# Sheet1.net
KiCad netlist of a schematic drawn in Altium Designer
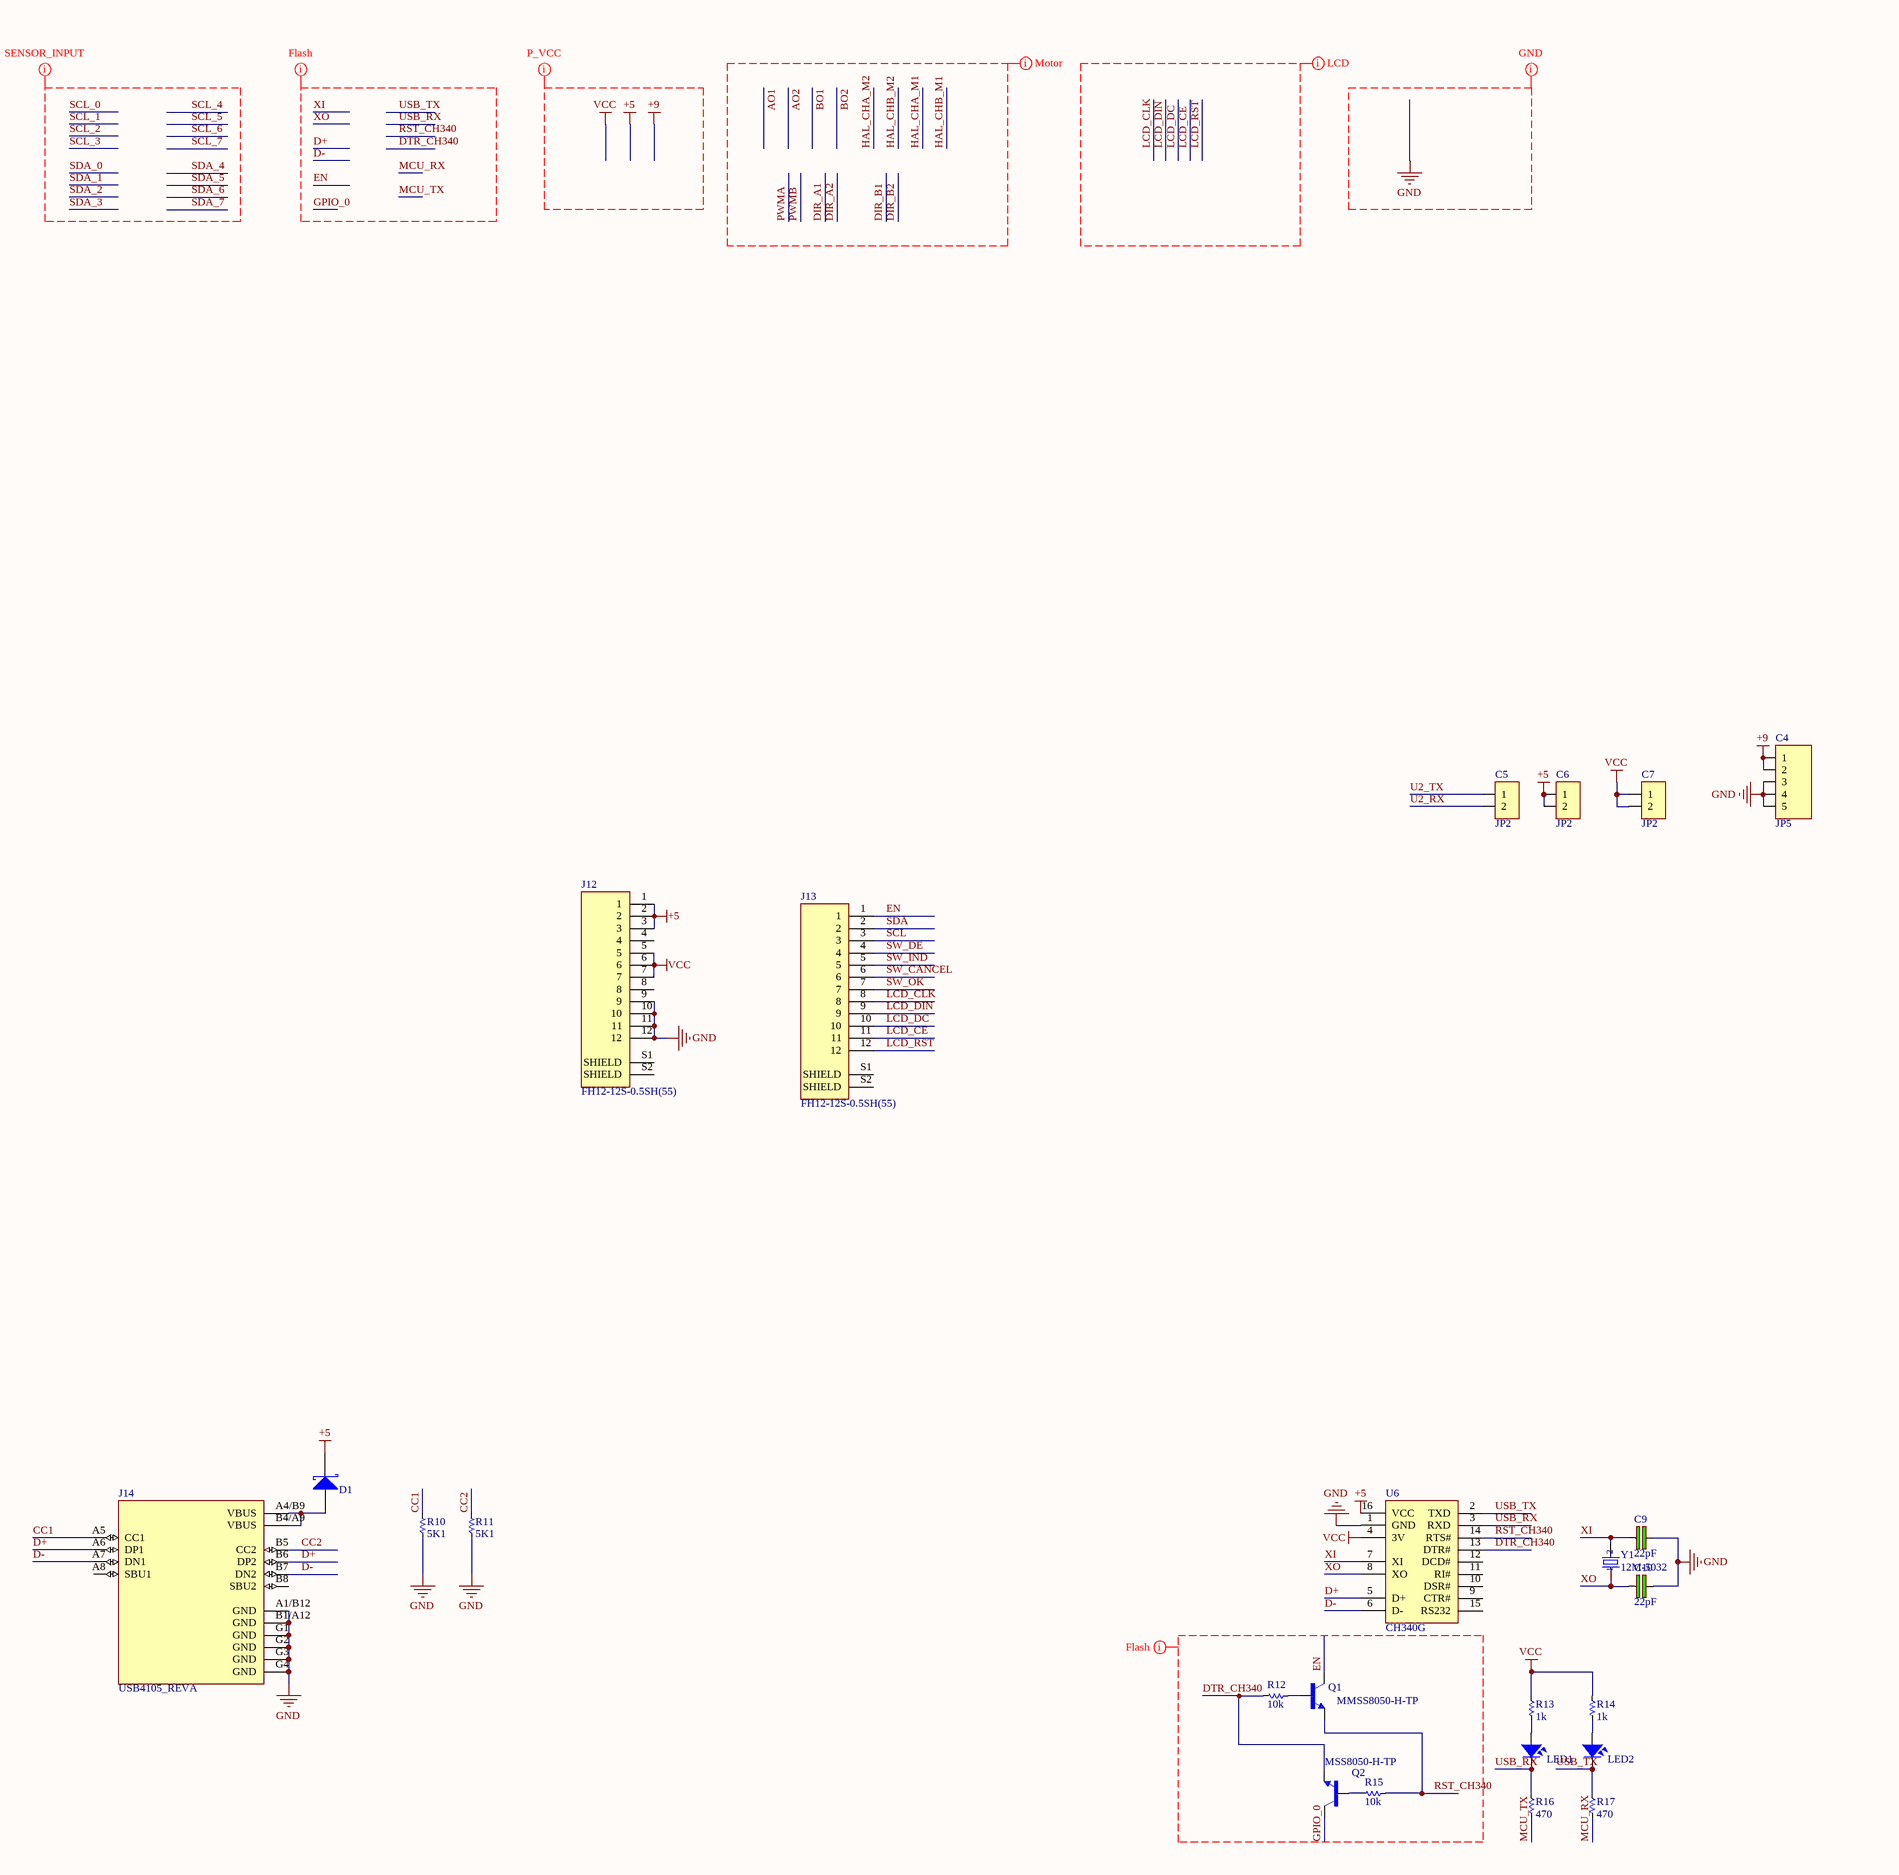
[diagram p0: Sheet1.SchDoc, left]
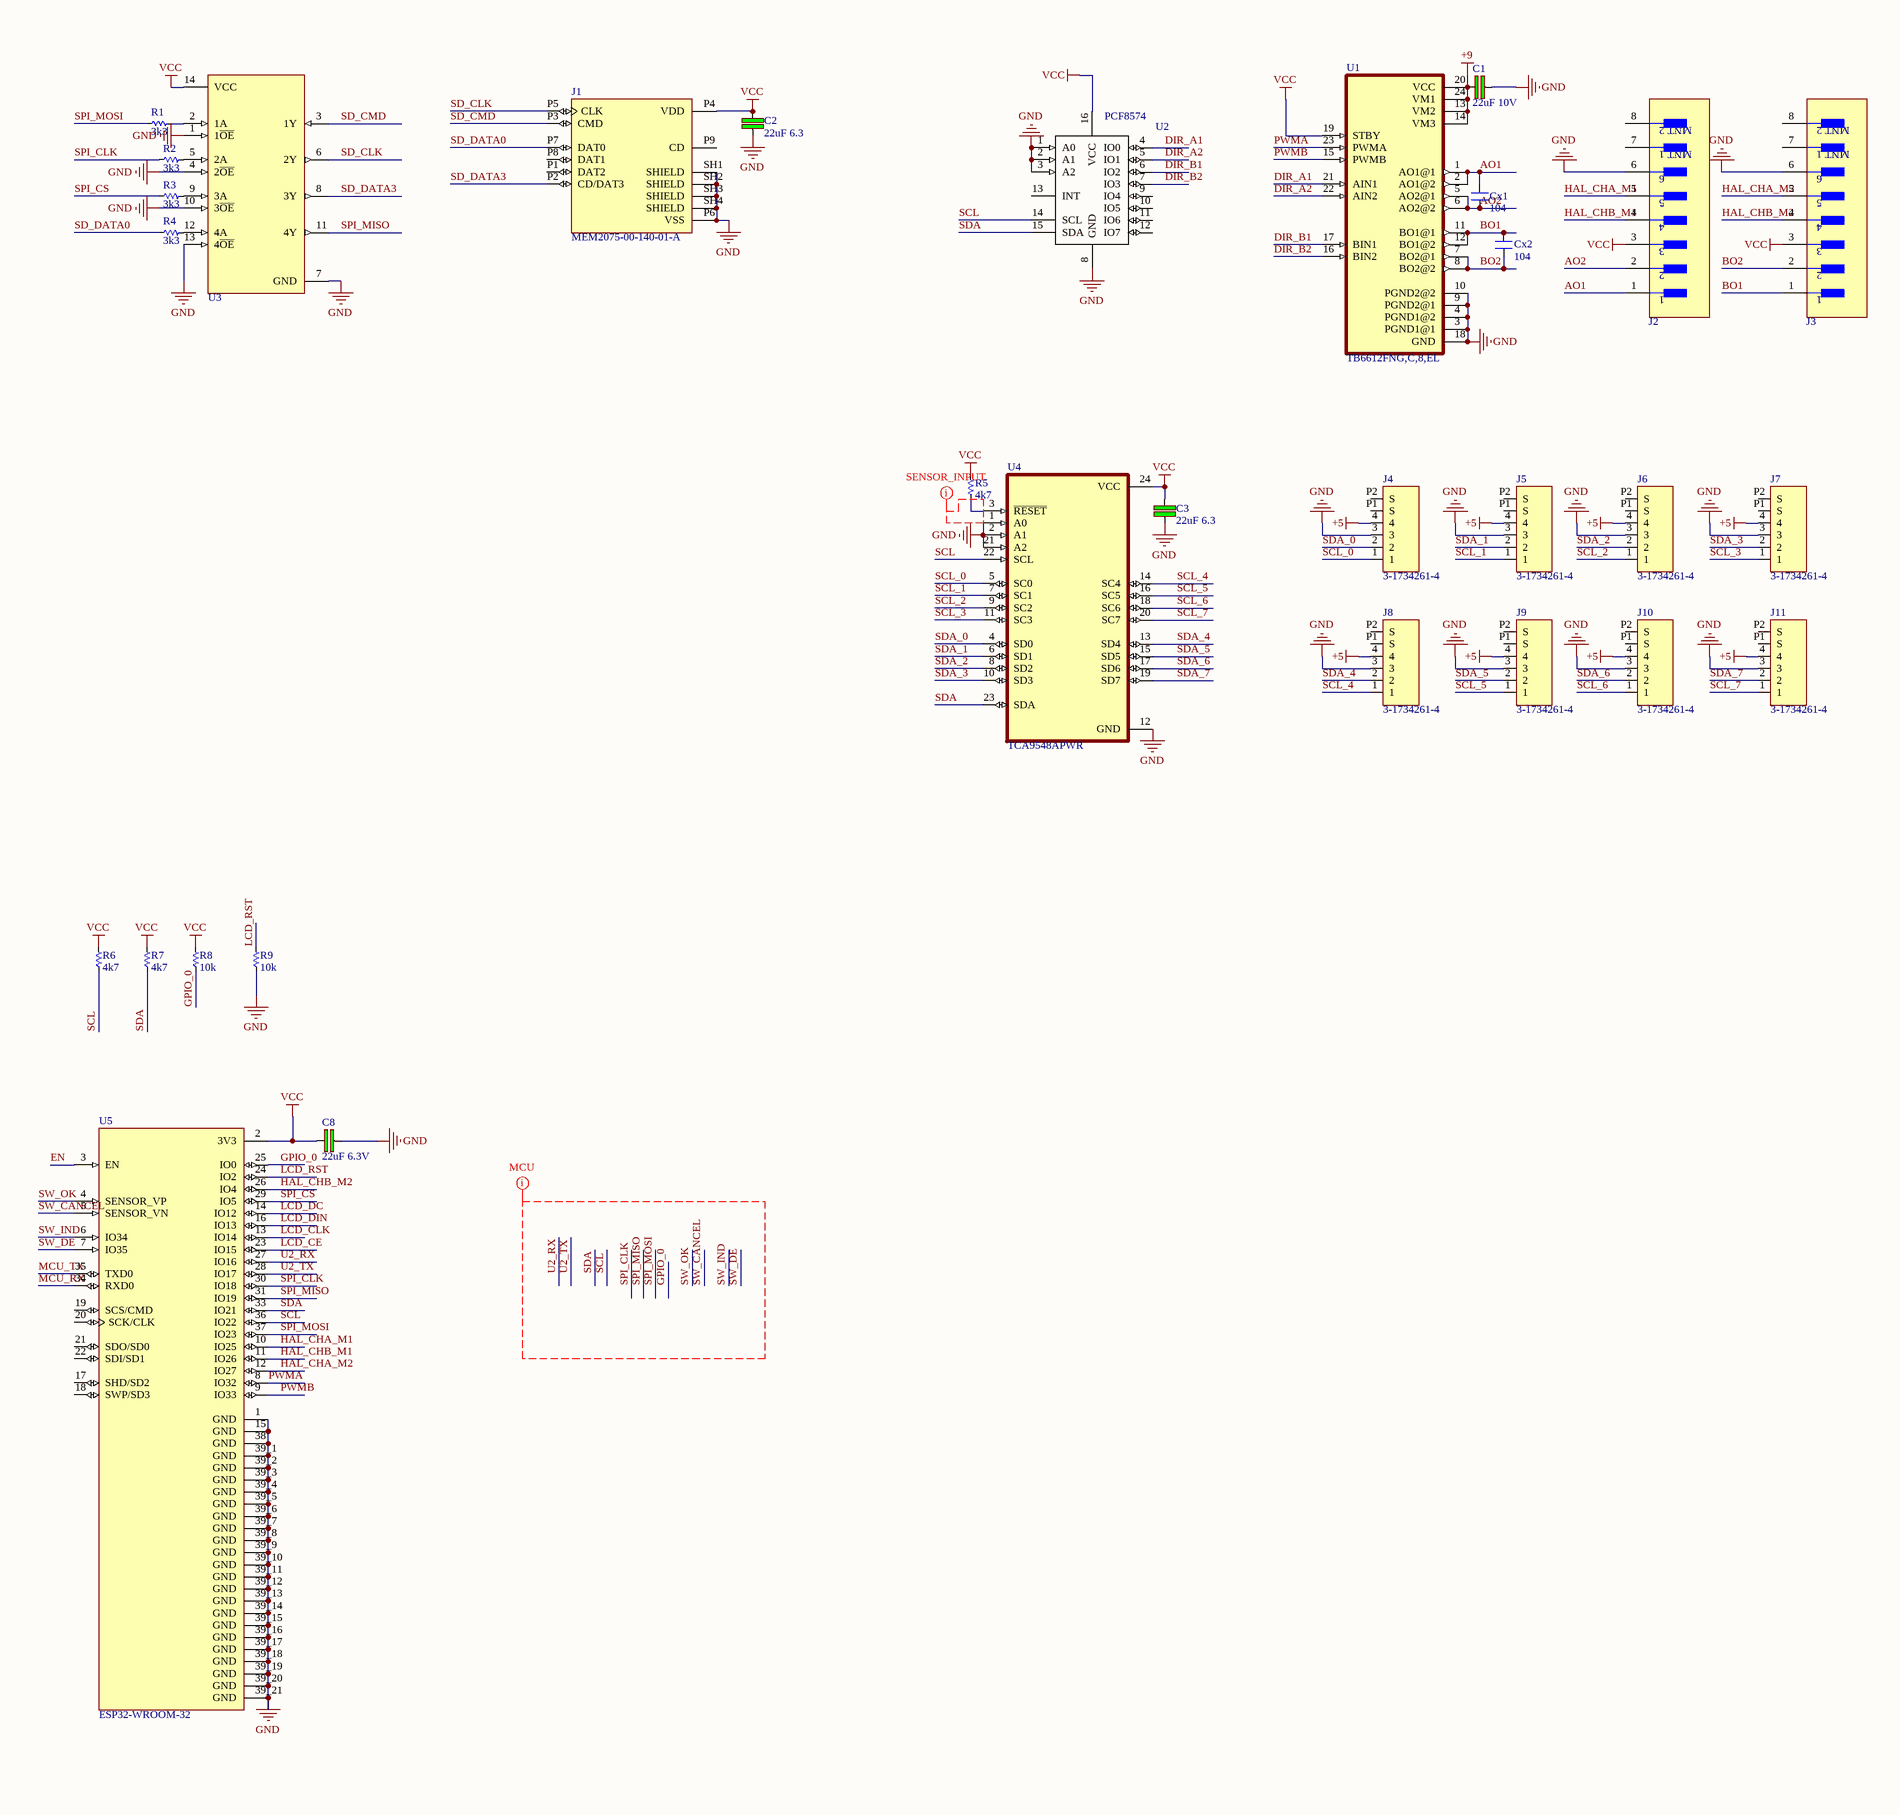
[diagram p1: Sheet1.SchDoc, right]

(export (version "E")
  (design (tool "Eeschema 10.0.6"))
  (components
    (comp (ref "C1")
      (value "22uF 10V")
      (footprint "CN-SMD-1206")
      (description "Cap SMD 1206 >5V")
      (libsource (lib "Library AL") (part "C"))
    )
    (comp (ref "C2")
      (value "22uF 6.3")
      (footprint "CN-SMD-1206")
      (description "Cap SMD 1206 >5V")
      (libsource (lib "") (part "C_2"))
    )
    (comp (ref "C3")
      (value "22uF 6.3")
      (footprint "CN-SMD-1206")
      (description "Cap SMD 1206 >5V")
      (libsource (lib "") (part "C_2"))
    )
    (comp (ref "C4")
      (value "JP5")
      (footprint "JP5-D1T")
      (description "WR-PHD 2.54 mm Angled Socket Header")
      (fields
        (field (name "MANUFACTURER") "Würth Elektronik eiSos GmbH")
        (field (name "PARTNO") "613005143121")
        (field (name "CREATED BY") "Karrer Zheng")
      )
      (libsource (lib "TechMT.VN_Lib_Project v2") (part "JP5"))
    )
    (comp (ref "C5")
      (value "JP2")
      (footprint "JP2-D1T")
      (description "WR-PHD 2.54 mm Angled Socket Header")
      (fields
        (field (name "MANUFACTURER") "Würth Elektronik eiSos GmbH")
        (field (name "PARTNO") "613002143121")
        (field (name "CREATED BY") "Karrer Zheng")
      )
      (libsource (lib "TechMT.VN_Lib_Project v2") (part "JP2"))
    )
    (comp (ref "C6")
      (value "JP2")
      (footprint "JP2-D1T")
      (description "WR-PHD 2.54 mm Angled Socket Header")
      (fields
        (field (name "MANUFACTURER") "Würth Elektronik eiSos GmbH")
        (field (name "PARTNO") "613002143121")
        (field (name "CREATED BY") "Karrer Zheng")
      )
      (libsource (lib "TechMT.VN_Lib_Project v2") (part "JP2"))
    )
    (comp (ref "C7")
      (value "JP2")
      (footprint "JP2-D1T")
      (description "WR-PHD 2.54 mm Angled Socket Header")
      (fields
        (field (name "MANUFACTURER") "Würth Elektronik eiSos GmbH")
        (field (name "PARTNO") "613002143121")
        (field (name "CREATED BY") "Karrer Zheng")
      )
      (libsource (lib "TechMT.VN_Lib_Project v2") (part "JP2"))
    )
    (comp (ref "C8")
      (value "22uF 6.3V")
      (footprint "CN-SMD-1206")
      (description "Cap SMD 1206 >5V")
      (libsource (lib "Library AL") (part "C"))
    )
    (comp (ref "C9")
      (value "22pF")
      (footprint "CN-SMD-0603")
      (description "Cap SMD")
      (libsource (lib "") (part "C_1"))
    )
    (comp (ref "C10")
      (value "22pF")
      (footprint "CN-SMD-0603")
      (description "Cap SMD")
      (libsource (lib "") (part "C_1"))
    )
    (comp (ref "Cx1") (value "104") (footprint "CN-SMD-0603") (libsource (lib "LIBRARY") (part "CN")))
    (comp (ref "Cx2") (value "104") (footprint "CN-SMD-0603") (libsource (lib "LIBRARY") (part "CN")))
    (comp (ref "D1")
      (value "D Schottky")
      (footprint "SS34")
      (description "Schottky Diode")
      (fields (field (name "PUBLISHER") "Altium Limited"))
      (libsource (lib "TechMT.VN_Lib_Project v1.0") (part "D Schottky"))
    )
    (comp (ref "J1")
      (value "MEM2075-00-140-01-A")
      (footprint "GCT_MEM2075-00-140-01-A")
      (description "9 _8 + 1_ Position Card Connector microSDâ„¢ Surface Mount, Right Angle Gold")
      (fields (field (name "MF") "Global Connector Technology"))
      (libsource (lib "micSDCARD01") (part "MEM2075-00-140-01-A"))
    )
    (comp (ref "J2")
      (value "532610671")
      (footprint "Molex_0_MFG")
      (libsource (lib "Conn_Molex_532610671_eec") (part "532610671"))
    )
    (comp (ref "J3")
      (value "532610671")
      (footprint "Molex_0_MFG")
      (libsource (lib "Conn_Molex_532610671_eec") (part "532610671"))
    )
    (comp (ref "J4")
      (value "3-1734261-4")
      (footprint "TE_3-1734261-4")
      (description "4ä½å•æŽ’1.25mmç›´è§’è¡¨é¢å®‰è£…æŽ¥å¤´è¿žæŽ¥å™¨")
      (fields (field (name "MF") "TE Connectivity"))
      (libsource (lib "hdr_4P_1.25m") (part "3-1734261-4"))
    )
    (comp (ref "J5")
      (value "3-1734261-4")
      (footprint "TE_3-1734261-4")
      (description "4ä½å•æŽ’1.25mmç›´è§’è¡¨é¢å®‰è£…æŽ¥å¤´è¿žæŽ¥å™¨")
      (fields (field (name "MF") "TE Connectivity"))
      (libsource (lib "hdr_4P_1.25m") (part "3-1734261-4"))
    )
    (comp (ref "J6")
      (value "3-1734261-4")
      (footprint "TE_3-1734261-4")
      (description "4ä½å•æŽ’1.25mmç›´è§’è¡¨é¢å®‰è£…æŽ¥å¤´è¿žæŽ¥å™¨")
      (fields (field (name "MF") "TE Connectivity"))
      (libsource (lib "hdr_4P_1.25m") (part "3-1734261-4"))
    )
    (comp (ref "J7")
      (value "3-1734261-4")
      (footprint "TE_3-1734261-4")
      (description "4ä½å•æŽ’1.25mmç›´è§’è¡¨é¢å®‰è£…æŽ¥å¤´è¿žæŽ¥å™¨")
      (fields (field (name "MF") "TE Connectivity"))
      (libsource (lib "hdr_4P_1.25m") (part "3-1734261-4"))
    )
    (comp (ref "J8")
      (value "3-1734261-4")
      (footprint "TE_3-1734261-4")
      (description "4ä½å•æŽ’1.25mmç›´è§’è¡¨é¢å®‰è£…æŽ¥å¤´è¿žæŽ¥å™¨")
      (fields (field (name "MF") "TE Connectivity"))
      (libsource (lib "hdr_4P_1.25m") (part "3-1734261-4"))
    )
    (comp (ref "J9")
      (value "3-1734261-4")
      (footprint "TE_3-1734261-4")
      (description "4ä½å•æŽ’1.25mmç›´è§’è¡¨é¢å®‰è£…æŽ¥å¤´è¿žæŽ¥å™¨")
      (fields (field (name "MF") "TE Connectivity"))
      (libsource (lib "hdr_4P_1.25m") (part "3-1734261-4"))
    )
    (comp (ref "J10")
      (value "3-1734261-4")
      (footprint "TE_3-1734261-4")
      (description "4ä½å•æŽ’1.25mmç›´è§’è¡¨é¢å®‰è£…æŽ¥å¤´è¿žæŽ¥å™¨")
      (fields (field (name "MF") "TE Connectivity"))
      (libsource (lib "hdr_4P_1.25m") (part "3-1734261-4"))
    )
    (comp (ref "J11")
      (value "3-1734261-4")
      (footprint "TE_3-1734261-4")
      (description "4ä½å•æŽ’1.25mmç›´è§’è¡¨é¢å®‰è£…æŽ¥å¤´è¿žæŽ¥å™¨")
      (fields (field (name "MF") "TE Connectivity"))
      (libsource (lib "hdr_4P_1.25m") (part "3-1734261-4"))
    )
    (comp (ref "J12")
      (value "FH12-12S-0.5SH(55)")
      (footprint "HIROSE_FH12-12S-0.5SH(55)")
      (description "12 Position FFC, FPC Connector Contacts, Bottom 0.020 _0.50mm_ Surface Mount, Right Angle")
      (fields (field (name "MF") "Hirose") (field (name "MP") "FH12-12S-0.5SH_55_"))
      (libsource (lib "FPC_SOC_12pos0.5") (part "FH12-12S-0.5SH(55)"))
    )
    (comp (ref "J13")
      (value "FH12-12S-0.5SH(55)")
      (footprint "HIROSE_FH12-12S-0.5SH(55)")
      (description "12 Position FFC, FPC Connector Contacts, Bottom 0.020 _0.50mm_ Surface Mount, Right Angle")
      (fields (field (name "MF") "Hirose") (field (name "MP") "FH12-12S-0.5SH_55_"))
      (libsource (lib "FPC_SOC_12pos0.5") (part "FH12-12S-0.5SH(55)"))
    )
    (comp (ref "J14")
      (value "USB4105_REVA")
      (footprint "GCT_USB4105_REVA")
      (fields (field (name "MF") "Global Connector Technology") (field (name "MP") "USB4105"))
      (libsource (lib "usb_typeC2.0B") (part "USB4105_REVA"))
    )
    (comp (ref "LED1")
      (value "LED")
      (footprint "LED-0805-Red")
      (libsource (lib "TechMT.VN_Lib_Project v2") (part "LED SMD"))
    )
    (comp (ref "LED2")
      (value "LED")
      (footprint "LED-0805-Red")
      (libsource (lib "TechMT.VN_Lib_Project v2") (part "LED SMD"))
    )
    (comp (ref "Q1")
      (value "MMSS8050-H-TP")
      (footprint "TRANS_MMSS8050-H-TP")
      (description "Bipolar _BJT_ Transistor NPN 25V 1.5A 100MHz 625mW Surface Mount SOT-23")
      (fields (field (name "MF") "Micro Commercial"))
      (libsource (lib "s8050") (part "MMSS8050-H-TP"))
    )
    (comp (ref "Q2")
      (value "MSS8050-H-TP")
      (footprint "TRANS_MMSS8050-H-TP")
      (description "Bipolar _BJT_ Transistor NPN 25V 1.5A 100MHz 625mW Surface Mount SOT-23")
      (fields (field (name "MF") "Micro Commercial") (field (name "MP") "MMSS8050-H-TP"))
      (libsource (lib "") (part "MMSS8050-H-TP_1"))
    )
    (comp (ref "R1")
      (value "3k3")
      (footprint "RES-SMD-0603")
      (description "Resistor")
      (fields
        (field (name "MANUFACTURER") "Generic Components")
        (field (name "PUBLISHER") "Altium Hobart Technology Centre")
      )
      (libsource (lib "My Library") (part "Res-SMD"))
    )
    (comp (ref "R2")
      (value "3k3")
      (footprint "RES-SMD-0603")
      (description "Resistor")
      (fields
        (field (name "MANUFACTURER") "Generic Components")
        (field (name "PUBLISHER") "Altium Hobart Technology Centre")
      )
      (libsource (lib "My Library") (part "Res-SMD"))
    )
    (comp (ref "R3")
      (value "3k3")
      (footprint "RES-SMD-0603")
      (description "Resistor")
      (fields
        (field (name "MANUFACTURER") "Generic Components")
        (field (name "PUBLISHER") "Altium Hobart Technology Centre")
      )
      (libsource (lib "My Library") (part "Res-SMD"))
    )
    (comp (ref "R4")
      (value "3k3")
      (footprint "RES-SMD-0603")
      (description "Resistor")
      (fields
        (field (name "MANUFACTURER") "Generic Components")
        (field (name "PUBLISHER") "Altium Hobart Technology Centre")
      )
      (libsource (lib "My Library") (part "Res-SMD"))
    )
    (comp (ref "R5")
      (value "4k7")
      (footprint "RES-SMD-0603")
      (description "Resistor")
      (fields
        (field (name "MANUFACTURER") "Generic Components")
        (field (name "PUBLISHER") "Altium Hobart Technology Centre")
      )
      (libsource (lib "My Library") (part "Res-SMD"))
    )
    (comp (ref "R6")
      (value "4k7")
      (footprint "RES-SMD-0603")
      (description "Resistor")
      (fields
        (field (name "MANUFACTURER") "Generic Components")
        (field (name "PUBLISHER") "Altium Hobart Technology Centre")
      )
      (libsource (lib "My Library") (part "Res-SMD"))
    )
    (comp (ref "R7")
      (value "4k7")
      (footprint "RES-SMD-0603")
      (description "Resistor")
      (fields
        (field (name "MANUFACTURER") "Generic Components")
        (field (name "PUBLISHER") "Altium Hobart Technology Centre")
      )
      (libsource (lib "My Library") (part "Res-SMD"))
    )
    (comp (ref "R8")
      (value "10k")
      (footprint "RES-SMD-0603")
      (description "Resistor")
      (fields
        (field (name "MANUFACTURER") "Generic Components")
        (field (name "PUBLISHER") "Altium Hobart Technology Centre")
      )
      (libsource (lib "My Library") (part "Res-SMD"))
    )
    (comp (ref "R9")
      (value "10k")
      (footprint "RES-SMD-0603")
      (description "Resistor")
      (fields
        (field (name "MANUFACTURER") "Generic Components")
        (field (name "PUBLISHER") "Altium Hobart Technology Centre")
      )
      (libsource (lib "My Library") (part "Res-SMD"))
    )
    (comp (ref "R10")
      (value "5K1")
      (footprint "RES-SMD-0603")
      (description "Resistor")
      (fields
        (field (name "MANUFACTURER") "Generic Components")
        (field (name "PUBLISHER") "Altium Hobart Technology Centre")
      )
      (libsource (lib "My Library") (part "Res-SMD"))
    )
    (comp (ref "R11")
      (value "5K1")
      (footprint "RES-SMD-0603")
      (description "Resistor")
      (fields
        (field (name "MANUFACTURER") "Generic Components")
        (field (name "PUBLISHER") "Altium Hobart Technology Centre")
      )
      (libsource (lib "My Library") (part "Res-SMD"))
    )
    (comp (ref "R12")
      (value "10k")
      (footprint "RES-SMD-0603")
      (description "Resistor")
      (fields
        (field (name "MANUFACTURER") "Generic Components")
        (field (name "PUBLISHER") "Altium Hobart Technology Centre")
      )
      (libsource (lib "My Library") (part "Res-SMD"))
    )
    (comp (ref "R13")
      (value "1k")
      (footprint "RES-SMD-0603")
      (description "Resistor")
      (fields
        (field (name "MANUFACTURER") "Generic Components")
        (field (name "PUBLISHER") "Altium Hobart Technology Centre")
      )
      (libsource (lib "My Library") (part "Res-SMD"))
    )
    (comp (ref "R14")
      (value "1k")
      (footprint "RES-SMD-0603")
      (description "Resistor")
      (fields
        (field (name "MANUFACTURER") "Generic Components")
        (field (name "PUBLISHER") "Altium Hobart Technology Centre")
      )
      (libsource (lib "My Library") (part "Res-SMD"))
    )
    (comp (ref "R15")
      (value "10k")
      (footprint "RES-SMD-0603")
      (description "Resistor")
      (fields
        (field (name "MANUFACTURER") "Generic Components")
        (field (name "PUBLISHER") "Altium Hobart Technology Centre")
      )
      (libsource (lib "My Library") (part "Res-SMD"))
    )
    (comp (ref "R16")
      (value "470")
      (footprint "RES-SMD-0603")
      (description "Resistor")
      (fields
        (field (name "MANUFACTURER") "Generic Components")
        (field (name "PUBLISHER") "Altium Hobart Technology Centre")
      )
      (libsource (lib "My Library") (part "Res-SMD"))
    )
    (comp (ref "R17")
      (value "470")
      (footprint "RES-SMD-0603")
      (description "Resistor")
      (fields
        (field (name "MANUFACTURER") "Generic Components")
        (field (name "PUBLISHER") "Altium Hobart Technology Centre")
      )
      (libsource (lib "My Library") (part "Res-SMD"))
    )
    (comp (ref "U1")
      (value "TB6612FNG,C,8,EL")
      (footprint "SOP65P760X160-24N")
      (description "Motor Driver Power MOSFET Parallel 24-SSOP")
      (fields (field (name "DIGI-KEY_PART_NUMBER") "TB6612FNGC8ELCT-ND") (field (name "MF") "Toshiba"))
      (libsource (lib "TB6612FNG_C_8_EL") (part "TB6612FNG,C,8,EL"))
    )
    (comp (ref "U2")
      (value "PCF8574")
      (footprint "SO16L")
      (description "I2C PORT EXPANDER")
      (fields
        (field (name "MANUFACTURER PART NUMBER") "PCF8574T/3,512")
        (field (name "MANUFACTURER") "NXP Semiconductors")
      )
      (libsource (lib "TechMT.VN_Lib_Project v2") (part "PCF8574"))
    )
    (comp (ref "U3")
      (value "SN74HC125PWR")
      (footprint "Texas_Instruments_PW0014A_MFG")
      (libsource (lib "IC_Texas_Instruments_SN74HC125PWR_eec") (part "SN74HC125PWR"))
    )
    (comp (ref "U4")
      (value "TCA9548APWR")
      (footprint "SOP65P640X120-24N")
      (description "Low-Voltage 8-Channel I2C Switch With Reset")
      (fields (field (name "MF") "Texas Instruments"))
      (libsource (lib "TCA9548APWR") (part "TCA9548APWR"))
    )
    (comp (ref "U5")
      (value "ESP32-WROOM-32")
      (footprint "MODULE_ESP32-WROOM-32")
      (description "Bluetooth, WiFi Transceiver Module 2.4GHz ~ 2.5GHz Surface Mount")
      (fields (field (name "MF") "Espressif Systems") (field (name "DIGI-KEY_PART_NUMBER") "1904-1010-1-ND"))
      (libsource (lib "ESP32-WROOM-32") (part "ESP32-WROOM-32"))
    )
    (comp (ref "U6")
      (value "CH340G")
      (footprint "SO16")
      (description "High and Low Side Driver")
      (fields (field (name "PUBLISHER") "Altium Limited"))
      (libsource (lib "TechMT.VN_Lib_Project v2") (part "CH340G"))
    )
    (comp (ref "Y1")
      (value "12M-5032")
      (footprint "X2-SMD-5.0X3.2X1.3MM")
      (description "SMD Crystal 8MHz-20pF-20ppm;")
      (fields (field (name "MF") "Xinhunjing") (field (name "MP") "5032/4P"))
      (libsource (lib "SMD-CRYSTAL-8MHZ-20PF-20PPM_2P-5.0X3.2MM_") (part "SMD-CRYSTAL-8MHZ-20PF-20PPM(2P-5.0X3.2MM)"))
    )
  )
  (nets
    (net (code "1") (name "+5") (class "Default")
      (node (ref "C6") (pin "1") (pinfunction "1_1") (pintype "passive"))
      (node (ref "C6") (pin "2") (pinfunction "2_2") (pintype "passive"))
      (node (ref "D1") (pin "2") (pinfunction "K_2") (pintype "passive"))
      (node (ref "J10") (pin "4") (pinfunction "4_4") (pintype "passive"))
      (node (ref "J11") (pin "4") (pinfunction "4_4") (pintype "passive"))
      (node (ref "J12") (pin "1") (pinfunction "1_1") (pintype "passive"))
      (node (ref "J12") (pin "2") (pinfunction "2_2") (pintype "passive"))
      (node (ref "J12") (pin "3") (pinfunction "3_3") (pintype "passive"))
      (node (ref "J4") (pin "4") (pinfunction "4_4") (pintype "passive"))
      (node (ref "J5") (pin "4") (pinfunction "4_4") (pintype "passive"))
      (node (ref "J6") (pin "4") (pinfunction "4_4") (pintype "passive"))
      (node (ref "J7") (pin "4") (pinfunction "4_4") (pintype "passive"))
      (node (ref "J8") (pin "4") (pinfunction "4_4") (pintype "passive"))
      (node (ref "J9") (pin "4") (pinfunction "4_4") (pintype "passive"))
      (node (ref "U6") (pin "16") (pinfunction "VCC_16") (pintype "passive"))
    )
    (net (code "2") (name "+9") (class "Default")
      (node (ref "C1") (pin "2") (pinfunction "2_2") (pintype "passive"))
      (node (ref "C4") (pin "1") (pinfunction "1_1") (pintype "passive"))
      (node (ref "C4") (pin "2") (pinfunction "2_2") (pintype "passive"))
      (node (ref "U1") (pin "13") (pinfunction "VM2_13") (pintype "power_in"))
      (node (ref "U1") (pin "14") (pinfunction "VM3_14") (pintype "power_in"))
      (node (ref "U1") (pin "20") (pinfunction "VCC_20") (pintype "power_in"))
      (node (ref "U1") (pin "24") (pinfunction "VM1_24") (pintype "power_in"))
    )
    (net (code "3") (name "/AO1") (class "Default")
      (node (ref "Cx1") (pin "2") (pinfunction "2_2") (pintype "passive"))
      (node (ref "J2") (pin "1") (pinfunction "1_1") (pintype "passive"))
      (node (ref "U1") (pin "1") (pinfunction "AO1@1_1") (pintype "output"))
      (node (ref "U1") (pin "2") (pinfunction "AO1@2_2") (pintype "output"))
    )
    (net (code "4") (name "/AO2") (class "Default")
      (node (ref "Cx1") (pin "1") (pinfunction "1_1") (pintype "passive"))
      (node (ref "J2") (pin "2") (pinfunction "2_2") (pintype "passive"))
      (node (ref "U1") (pin "5") (pinfunction "AO2@1_5") (pintype "output"))
      (node (ref "U1") (pin "6") (pinfunction "AO2@2_6") (pintype "output"))
    )
    (net (code "5") (name "/BO1") (class "Default")
      (node (ref "Cx2") (pin "2") (pinfunction "2_2") (pintype "passive"))
      (node (ref "J3") (pin "1") (pinfunction "1_1") (pintype "passive"))
      (node (ref "U1") (pin "11") (pinfunction "BO1@1_11") (pintype "output"))
      (node (ref "U1") (pin "12") (pinfunction "BO1@2_12") (pintype "output"))
    )
    (net (code "6") (name "/BO2") (class "Default")
      (node (ref "Cx2") (pin "1") (pinfunction "1_1") (pintype "passive"))
      (node (ref "J3") (pin "2") (pinfunction "2_2") (pintype "passive"))
      (node (ref "U1") (pin "7") (pinfunction "BO2@1_7") (pintype "output"))
      (node (ref "U1") (pin "8") (pinfunction "BO2@2_8") (pintype "output"))
    )
    (net (code "7") (name "/CC1") (class "Default")
      (node (ref "J14") (pin "A5") (pinfunction "CC1_A5") (pintype "bidirectional"))
      (node (ref "R10") (pin "2") (pinfunction "2_2") (pintype "passive"))
    )
    (net (code "8") (name "/CC2") (class "Default")
      (node (ref "J14") (pin "B5") (pinfunction "CC2_B5") (pintype "bidirectional"))
      (node (ref "R11") (pin "2") (pinfunction "2_2") (pintype "passive"))
    )
    (net (code "9") (name "/D+") (class "Default")
      (node (ref "J14") (pin "A6") (pinfunction "DP1_A6") (pintype "bidirectional"))
      (node (ref "J14") (pin "B6") (pinfunction "DP2_B6") (pintype "bidirectional"))
      (node (ref "U6") (pin "5") (pinfunction "D+_5") (pintype "passive"))
    )
    (net (code "10") (name "/D-") (class "Default")
      (node (ref "J14") (pin "A7") (pinfunction "DN1_A7") (pintype "bidirectional"))
      (node (ref "J14") (pin "B7") (pinfunction "DN2_B7") (pintype "bidirectional"))
      (node (ref "U6") (pin "6") (pinfunction "D-_6") (pintype "passive"))
    )
    (net (code "11") (name "/DIR_A1") (class "Default")
      (node (ref "U1") (pin "21") (pinfunction "AIN1_21") (pintype "input"))
      (node (ref "U2") (pin "4") (pinfunction "IO0_4") (pintype "bidirectional"))
    )
    (net (code "12") (name "/DIR_A2") (class "Default")
      (node (ref "U1") (pin "22") (pinfunction "AIN2_22") (pintype "input"))
      (node (ref "U2") (pin "5") (pinfunction "IO1_5") (pintype "bidirectional"))
    )
    (net (code "13") (name "/DIR_B1") (class "Default")
      (node (ref "U1") (pin "17") (pinfunction "BIN1_17") (pintype "input"))
      (node (ref "U2") (pin "6") (pinfunction "IO2_6") (pintype "bidirectional"))
    )
    (net (code "14") (name "/DIR_B2") (class "Default")
      (node (ref "U1") (pin "16") (pinfunction "BIN2_16") (pintype "input"))
      (node (ref "U2") (pin "7") (pinfunction "IO3_7") (pintype "bidirectional"))
    )
    (net (code "15") (name "/DTR_CH340") (class "Default")
      (node (ref "Q2") (pin "2") (pinfunction "E_2") (pintype "passive"))
      (node (ref "R12") (pin "1") (pinfunction "1_1") (pintype "passive"))
      (node (ref "U6") (pin "13") (pinfunction "DTR#_13") (pintype "passive"))
    )
    (net (code "16") (name "/EN") (class "Default")
      (node (ref "J13") (pin "1") (pinfunction "1_1") (pintype "passive"))
      (node (ref "Q1") (pin "3") (pinfunction "C_3") (pintype "passive"))
      (node (ref "U5") (pin "3") (pinfunction "EN_3") (pintype "input"))
    )
    (net (code "17") (name "/GPIO_0") (class "Default")
      (node (ref "Q2") (pin "3") (pinfunction "C_3") (pintype "passive"))
      (node (ref "R8") (pin "1") (pinfunction "1_1") (pintype "passive"))
      (node (ref "U5") (pin "25") (pinfunction "IO0_25") (pintype "bidirectional"))
    )
    (net (code "18") (name "/HAL_CHA_M1") (class "Default")
      (node (ref "J2") (pin "5") (pinfunction "5_5") (pintype "passive"))
      (node (ref "U5") (pin "10") (pinfunction "IO25_10") (pintype "bidirectional"))
    )
    (net (code "19") (name "/HAL_CHA_M2") (class "Default")
      (node (ref "J3") (pin "5") (pinfunction "5_5") (pintype "passive"))
      (node (ref "U5") (pin "12") (pinfunction "IO27_12") (pintype "bidirectional"))
    )
    (net (code "20") (name "/HAL_CHB_M1") (class "Default")
      (node (ref "J2") (pin "4") (pinfunction "4_4") (pintype "passive"))
      (node (ref "U5") (pin "11") (pinfunction "IO26_11") (pintype "bidirectional"))
    )
    (net (code "21") (name "/HAL_CHB_M2") (class "Default")
      (node (ref "J3") (pin "4") (pinfunction "4_4") (pintype "passive"))
      (node (ref "U5") (pin "26") (pinfunction "IO4_26") (pintype "bidirectional"))
    )
    (net (code "22") (name "/LCD_CE") (class "Default")
      (node (ref "J13") (pin "11") (pinfunction "11_11") (pintype "passive"))
      (node (ref "U5") (pin "23") (pinfunction "IO15_23") (pintype "bidirectional"))
    )
    (net (code "23") (name "/LCD_CLK") (class "Default")
      (node (ref "J13") (pin "8") (pinfunction "8_8") (pintype "passive"))
      (node (ref "U5") (pin "13") (pinfunction "IO14_13") (pintype "bidirectional"))
    )
    (net (code "24") (name "/LCD_DC") (class "Default")
      (node (ref "J13") (pin "10") (pinfunction "10_10") (pintype "passive"))
      (node (ref "U5") (pin "14") (pinfunction "IO12_14") (pintype "bidirectional"))
    )
    (net (code "25") (name "/LCD_DIN") (class "Default")
      (node (ref "J13") (pin "9") (pinfunction "9_9") (pintype "passive"))
      (node (ref "U5") (pin "16") (pinfunction "IO13_16") (pintype "bidirectional"))
    )
    (net (code "26") (name "/LCD_RST") (class "Default")
      (node (ref "J13") (pin "12") (pinfunction "12_12") (pintype "passive"))
      (node (ref "R9") (pin "2") (pinfunction "2_2") (pintype "passive"))
      (node (ref "U5") (pin "24") (pinfunction "IO2_24") (pintype "bidirectional"))
    )
    (net (code "27") (name "/MCU_RX") (class "Default")
      (node (ref "R17") (pin "1") (pinfunction "1_1") (pintype "passive"))
      (node (ref "U5") (pin "34") (pinfunction "RXD0_34") (pintype "bidirectional"))
    )
    (net (code "28") (name "/MCU_TX") (class "Default")
      (node (ref "R16") (pin "1") (pinfunction "1_1") (pintype "passive"))
      (node (ref "U5") (pin "35") (pinfunction "TXD0_35") (pintype "bidirectional"))
    )
    (net (code "29") (name "/PWMA") (class "Default")
      (node (ref "U1") (pin "23") (pinfunction "PWMA_23") (pintype "input"))
      (node (ref "U5") (pin "8") (pinfunction "IO32_8") (pintype "bidirectional"))
    )
    (net (code "30") (name "/PWMB") (class "Default")
      (node (ref "U1") (pin "15") (pinfunction "PWMB_15") (pintype "input"))
      (node (ref "U5") (pin "9") (pinfunction "IO33_9") (pintype "bidirectional"))
    )
    (net (code "31") (name "/RST_CH340") (class "Default")
      (node (ref "Q1") (pin "2") (pinfunction "E_2") (pintype "passive"))
      (node (ref "R15") (pin "2") (pinfunction "2_2") (pintype "passive"))
      (node (ref "U6") (pin "14") (pinfunction "RTS#_14") (pintype "passive"))
    )
    (net (code "32") (name "/SCL") (class "Default")
      (node (ref "J13") (pin "3") (pinfunction "3_3") (pintype "passive"))
      (node (ref "R6") (pin "1") (pinfunction "1_1") (pintype "passive"))
      (node (ref "U2") (pin "14") (pinfunction "SCL_14") (pintype "open_collector"))
      (node (ref "U4") (pin "22") (pinfunction "SCL_22") (pintype "input"))
      (node (ref "U5") (pin "36") (pinfunction "IO22_36") (pintype "bidirectional"))
    )
    (net (code "33") (name "/SCL_0") (class "Default")
      (node (ref "J4") (pin "1") (pinfunction "1_1") (pintype "passive"))
      (node (ref "U4") (pin "5") (pinfunction "SC0_5") (pintype "bidirectional"))
    )
    (net (code "34") (name "/SCL_1") (class "Default")
      (node (ref "J5") (pin "1") (pinfunction "1_1") (pintype "passive"))
      (node (ref "U4") (pin "7") (pinfunction "SC1_7") (pintype "bidirectional"))
    )
    (net (code "35") (name "/SCL_2") (class "Default")
      (node (ref "J6") (pin "1") (pinfunction "1_1") (pintype "passive"))
      (node (ref "U4") (pin "9") (pinfunction "SC2_9") (pintype "bidirectional"))
    )
    (net (code "36") (name "/SCL_3") (class "Default")
      (node (ref "J7") (pin "1") (pinfunction "1_1") (pintype "passive"))
      (node (ref "U4") (pin "11") (pinfunction "SC3_11") (pintype "bidirectional"))
    )
    (net (code "37") (name "/SCL_4") (class "Default")
      (node (ref "J8") (pin "1") (pinfunction "1_1") (pintype "passive"))
      (node (ref "U4") (pin "14") (pinfunction "SC4_14") (pintype "bidirectional"))
    )
    (net (code "38") (name "/SCL_5") (class "Default")
      (node (ref "J9") (pin "1") (pinfunction "1_1") (pintype "passive"))
      (node (ref "U4") (pin "16") (pinfunction "SC5_16") (pintype "bidirectional"))
    )
    (net (code "39") (name "/SCL_6") (class "Default")
      (node (ref "J10") (pin "1") (pinfunction "1_1") (pintype "passive"))
      (node (ref "U4") (pin "18") (pinfunction "SC6_18") (pintype "bidirectional"))
    )
    (net (code "40") (name "/SCL_7") (class "Default")
      (node (ref "J11") (pin "1") (pinfunction "1_1") (pintype "passive"))
      (node (ref "U4") (pin "20") (pinfunction "SC7_20") (pintype "bidirectional"))
    )
    (net (code "41") (name "/SDA") (class "Default")
      (node (ref "J13") (pin "2") (pinfunction "2_2") (pintype "passive"))
      (node (ref "R7") (pin "1") (pinfunction "1_1") (pintype "passive"))
      (node (ref "U2") (pin "15") (pinfunction "SDA_15") (pintype "open_collector"))
      (node (ref "U4") (pin "23") (pinfunction "SDA_23") (pintype "bidirectional"))
      (node (ref "U5") (pin "33") (pinfunction "IO21_33") (pintype "bidirectional"))
    )
    (net (code "42") (name "/SDA_0") (class "Default")
      (node (ref "J4") (pin "2") (pinfunction "2_2") (pintype "passive"))
      (node (ref "U4") (pin "4") (pinfunction "SD0_4") (pintype "bidirectional"))
    )
    (net (code "43") (name "/SDA_1") (class "Default")
      (node (ref "J5") (pin "2") (pinfunction "2_2") (pintype "passive"))
      (node (ref "U4") (pin "6") (pinfunction "SD1_6") (pintype "bidirectional"))
    )
    (net (code "44") (name "/SDA_2") (class "Default")
      (node (ref "J6") (pin "2") (pinfunction "2_2") (pintype "passive"))
      (node (ref "U4") (pin "8") (pinfunction "SD2_8") (pintype "bidirectional"))
    )
    (net (code "45") (name "/SDA_3") (class "Default")
      (node (ref "J7") (pin "2") (pinfunction "2_2") (pintype "passive"))
      (node (ref "U4") (pin "10") (pinfunction "SD3_10") (pintype "bidirectional"))
    )
    (net (code "46") (name "/SDA_4") (class "Default")
      (node (ref "J8") (pin "2") (pinfunction "2_2") (pintype "passive"))
      (node (ref "U4") (pin "13") (pinfunction "SD4_13") (pintype "bidirectional"))
    )
    (net (code "47") (name "/SDA_5") (class "Default")
      (node (ref "J9") (pin "2") (pinfunction "2_2") (pintype "passive"))
      (node (ref "U4") (pin "15") (pinfunction "SD5_15") (pintype "bidirectional"))
    )
    (net (code "48") (name "/SDA_6") (class "Default")
      (node (ref "J10") (pin "2") (pinfunction "2_2") (pintype "passive"))
      (node (ref "U4") (pin "17") (pinfunction "SD6_17") (pintype "bidirectional"))
    )
    (net (code "49") (name "/SDA_7") (class "Default")
      (node (ref "J11") (pin "2") (pinfunction "2_2") (pintype "passive"))
      (node (ref "U4") (pin "19") (pinfunction "SD7_19") (pintype "bidirectional"))
    )
    (net (code "50") (name "/SD_CLK") (class "Default")
      (node (ref "J1") (pin "P5") (pinfunction "CLK_P5") (pintype "bidirectional"))
      (node (ref "U3") (pin "6") (pinfunction "2Y_6") (pintype "output"))
    )
    (net (code "51") (name "/SD_CMD") (class "Default")
      (node (ref "J1") (pin "P3") (pinfunction "CMD_P3") (pintype "bidirectional"))
      (node (ref "U3") (pin "3") (pinfunction "1Y_3") (pintype "input"))
    )
    (net (code "52") (name "/SD_DATA0") (class "Default")
      (node (ref "J1") (pin "P7") (pinfunction "DAT0_P7") (pintype "bidirectional"))
      (node (ref "R4") (pin "2") (pinfunction "2_2") (pintype "passive"))
    )
    (net (code "53") (name "/SD_DATA3") (class "Default")
      (node (ref "J1") (pin "P2") (pinfunction "CD/DAT3_P2") (pintype "bidirectional"))
      (node (ref "U3") (pin "8") (pinfunction "3Y_8") (pintype "output"))
    )
    (net (code "54") (name "/SPI_CLK") (class "Default")
      (node (ref "R2") (pin "2") (pinfunction "2_2") (pintype "passive"))
      (node (ref "U5") (pin "30") (pinfunction "IO18_30") (pintype "bidirectional"))
    )
    (net (code "55") (name "/SPI_CS") (class "Default")
      (node (ref "R3") (pin "2") (pinfunction "2_2") (pintype "passive"))
      (node (ref "U5") (pin "29") (pinfunction "IO5_29") (pintype "bidirectional"))
    )
    (net (code "56") (name "/SPI_MISO") (class "Default")
      (node (ref "U3") (pin "11") (pinfunction "4Y_11") (pintype "output"))
      (node (ref "U5") (pin "31") (pinfunction "IO19_31") (pintype "bidirectional"))
    )
    (net (code "57") (name "/SPI_MOSI") (class "Default")
      (node (ref "R1") (pin "2") (pinfunction "2_2") (pintype "passive"))
      (node (ref "U5") (pin "37") (pinfunction "IO23_37") (pintype "bidirectional"))
    )
    (net (code "58") (name "/SW_CANCEL") (class "Default")
      (node (ref "J13") (pin "6") (pinfunction "6_6") (pintype "passive"))
      (node (ref "U5") (pin "5") (pinfunction "SENSOR_VN_5") (pintype "input"))
    )
    (net (code "59") (name "/SW_DE") (class "Default")
      (node (ref "J13") (pin "4") (pinfunction "4_4") (pintype "passive"))
      (node (ref "U5") (pin "7") (pinfunction "IO35_7") (pintype "input"))
    )
    (net (code "60") (name "/SW_IND") (class "Default")
      (node (ref "J13") (pin "5") (pinfunction "5_5") (pintype "passive"))
      (node (ref "U5") (pin "6") (pinfunction "IO34_6") (pintype "input"))
    )
    (net (code "61") (name "/SW_OK") (class "Default")
      (node (ref "J13") (pin "7") (pinfunction "7_7") (pintype "passive"))
      (node (ref "U5") (pin "4") (pinfunction "SENSOR_VP_4") (pintype "input"))
    )
    (net (code "62") (name "/U2_RX") (class "Default")
      (node (ref "C5") (pin "2") (pinfunction "2_2") (pintype "passive"))
      (node (ref "U5") (pin "27") (pinfunction "IO16_27") (pintype "bidirectional"))
    )
    (net (code "63") (name "/U2_TX") (class "Default")
      (node (ref "C5") (pin "1") (pinfunction "1_1") (pintype "passive"))
      (node (ref "U5") (pin "28") (pinfunction "IO17_28") (pintype "bidirectional"))
    )
    (net (code "64") (name "/USB_RX") (class "Default")
      (node (ref "LED1") (pin "2") (pinfunction "2_2") (pintype "passive"))
      (node (ref "R16") (pin "2") (pinfunction "2_2") (pintype "passive"))
      (node (ref "U6") (pin "3") (pinfunction "RXD_3") (pintype "passive"))
    )
    (net (code "65") (name "/USB_TX") (class "Default")
      (node (ref "LED2") (pin "2") (pinfunction "2_2") (pintype "passive"))
      (node (ref "R17") (pin "2") (pinfunction "2_2") (pintype "passive"))
      (node (ref "U6") (pin "2") (pinfunction "TXD_2") (pintype "passive"))
    )
    (net (code "66") (name "/XI") (class "Default")
      (node (ref "C9") (pin "1") (pinfunction "1_1") (pintype "passive"))
      (node (ref "U6") (pin "7") (pinfunction "XI_7") (pintype "passive"))
      (node (ref "Y1") (pin "2") (pinfunction "2_2") (pintype "passive"))
    )
    (net (code "67") (name "/XO") (class "Default")
      (node (ref "C10") (pin "1") (pinfunction "1_1") (pintype "passive"))
      (node (ref "U6") (pin "8") (pinfunction "XO_8") (pintype "passive"))
      (node (ref "Y1") (pin "1") (pinfunction "1_1") (pintype "passive"))
    )
    (net (code "68") (name "GND") (class "Default")
      (node (ref "C1") (pin "1") (pinfunction "1_1") (pintype "passive"))
      (node (ref "C10") (pin "2") (pinfunction "2_2") (pintype "passive"))
      (node (ref "C2") (pin "1") (pinfunction "1_1") (pintype "passive"))
      (node (ref "C3") (pin "1") (pinfunction "1_1") (pintype "passive"))
      (node (ref "C4") (pin "3") (pinfunction "3_3") (pintype "passive"))
      (node (ref "C4") (pin "4") (pinfunction "4_4") (pintype "passive"))
      (node (ref "C4") (pin "5") (pinfunction "5_5") (pintype "passive"))
      (node (ref "C8") (pin "1") (pinfunction "1_1") (pintype "passive"))
      (node (ref "C9") (pin "2") (pinfunction "2_2") (pintype "passive"))
      (node (ref "J1") (pin "P6") (pinfunction "VSS_P6") (pintype "power_in"))
      (node (ref "J1") (pin "SH1") (pinfunction "SHIELD_SH1") (pintype "power_in"))
      (node (ref "J1") (pin "SH2") (pinfunction "SHIELD_SH2") (pintype "power_in"))
      (node (ref "J1") (pin "SH3") (pinfunction "SHIELD_SH3") (pintype "power_in"))
      (node (ref "J1") (pin "SH4") (pinfunction "SHIELD_SH4") (pintype "power_in"))
      (node (ref "J10") (pin "3") (pinfunction "3_3") (pintype "passive"))
      (node (ref "J11") (pin "3") (pinfunction "3_3") (pintype "passive"))
      (node (ref "J12") (pin "10") (pinfunction "10_10") (pintype "passive"))
      (node (ref "J12") (pin "11") (pinfunction "11_11") (pintype "passive"))
      (node (ref "J12") (pin "12") (pinfunction "12_12") (pintype "passive"))
      (node (ref "J12") (pin "9") (pinfunction "9_9") (pintype "passive"))
      (node (ref "J14") (pin "A1/B12") (pinfunction "GND_A1/B12") (pintype "power_in"))
      (node (ref "J14") (pin "B1/A12") (pinfunction "GND_B1/A12") (pintype "power_in"))
      (node (ref "J14") (pin "G1") (pinfunction "GND_G1") (pintype "power_in"))
      (node (ref "J14") (pin "G2") (pinfunction "GND_G2") (pintype "power_in"))
      (node (ref "J14") (pin "G3") (pinfunction "GND_G3") (pintype "power_in"))
      (node (ref "J14") (pin "G4") (pinfunction "GND_G4") (pintype "power_in"))
      (node (ref "J2") (pin "6") (pinfunction "6_6") (pintype "passive"))
      (node (ref "J3") (pin "6") (pinfunction "6_6") (pintype "passive"))
      (node (ref "J4") (pin "3") (pinfunction "3_3") (pintype "passive"))
      (node (ref "J5") (pin "3") (pinfunction "3_3") (pintype "passive"))
      (node (ref "J6") (pin "3") (pinfunction "3_3") (pintype "passive"))
      (node (ref "J7") (pin "3") (pinfunction "3_3") (pintype "passive"))
      (node (ref "J8") (pin "3") (pinfunction "3_3") (pintype "passive"))
      (node (ref "J9") (pin "3") (pinfunction "3_3") (pintype "passive"))
      (node (ref "R10") (pin "1") (pinfunction "1_1") (pintype "passive"))
      (node (ref "R11") (pin "1") (pinfunction "1_1") (pintype "passive"))
      (node (ref "R9") (pin "1") (pinfunction "1_1") (pintype "passive"))
      (node (ref "U1") (pin "10") (pinfunction "PGND2@2_10") (pintype "passive"))
      (node (ref "U1") (pin "18") (pinfunction "GND_18") (pintype "passive"))
      (node (ref "U1") (pin "3") (pinfunction "PGND1@1_3") (pintype "passive"))
      (node (ref "U1") (pin "4") (pinfunction "PGND1@2_4") (pintype "passive"))
      (node (ref "U1") (pin "9") (pinfunction "PGND2@1_9") (pintype "passive"))
      (node (ref "U2") (pin "1") (pinfunction "A0_1") (pintype "input"))
      (node (ref "U2") (pin "2") (pinfunction "A1_2") (pintype "input"))
      (node (ref "U2") (pin "3") (pinfunction "A2_3") (pintype "input"))
      (node (ref "U2") (pin "8") (pinfunction "GND_8") (pintype "open_collector"))
      (node (ref "U3") (pin "1") (pinfunction "1~{OE}_1") (pintype "input"))
      (node (ref "U3") (pin "10") (pinfunction "3~{OE}_10") (pintype "input"))
      (node (ref "U3") (pin "13") (pinfunction "4~{OE}_13") (pintype "input"))
      (node (ref "U3") (pin "4") (pinfunction "2~{OE}_4") (pintype "input"))
      (node (ref "U3") (pin "7") (pinfunction "GND_7") (pintype "power_in"))
      (node (ref "U4") (pin "1") (pinfunction "A0_1") (pintype "input"))
      (node (ref "U4") (pin "12") (pinfunction "GND_12") (pintype "power_in"))
      (node (ref "U4") (pin "2") (pinfunction "A1_2") (pintype "input"))
      (node (ref "U4") (pin "21") (pinfunction "A2_21") (pintype "input"))
      (node (ref "U5") (pin "1") (pinfunction "GND_1") (pintype "power_in"))
      (node (ref "U5") (pin "15") (pinfunction "GND_15") (pintype "power_in"))
      (node (ref "U5") (pin "38") (pinfunction "GND_38") (pintype "power_in"))
      (node (ref "U5") (pin "39_1") (pinfunction "GND_39_1") (pintype "power_in"))
      (node (ref "U5") (pin "39_10") (pinfunction "GND_39_10") (pintype "power_in"))
      (node (ref "U5") (pin "39_11") (pinfunction "GND_39_11") (pintype "power_in"))
      (node (ref "U5") (pin "39_12") (pinfunction "GND_39_12") (pintype "power_in"))
      (node (ref "U5") (pin "39_13") (pinfunction "GND_39_13") (pintype "power_in"))
      (node (ref "U5") (pin "39_14") (pinfunction "GND_39_14") (pintype "power_in"))
      (node (ref "U5") (pin "39_15") (pinfunction "GND_39_15") (pintype "power_in"))
      (node (ref "U5") (pin "39_16") (pinfunction "GND_39_16") (pintype "power_in"))
      (node (ref "U5") (pin "39_17") (pinfunction "GND_39_17") (pintype "power_in"))
      (node (ref "U5") (pin "39_18") (pinfunction "GND_39_18") (pintype "power_in"))
      (node (ref "U5") (pin "39_19") (pinfunction "GND_39_19") (pintype "power_in"))
      (node (ref "U5") (pin "39_2") (pinfunction "GND_39_2") (pintype "power_in"))
      (node (ref "U5") (pin "39_20") (pinfunction "GND_39_20") (pintype "power_in"))
      (node (ref "U5") (pin "39_21") (pinfunction "GND_39_21") (pintype "power_in"))
      (node (ref "U5") (pin "39_3") (pinfunction "GND_39_3") (pintype "power_in"))
      (node (ref "U5") (pin "39_4") (pinfunction "GND_39_4") (pintype "power_in"))
      (node (ref "U5") (pin "39_5") (pinfunction "GND_39_5") (pintype "power_in"))
      (node (ref "U5") (pin "39_6") (pinfunction "GND_39_6") (pintype "power_in"))
      (node (ref "U5") (pin "39_7") (pinfunction "GND_39_7") (pintype "power_in"))
      (node (ref "U5") (pin "39_8") (pinfunction "GND_39_8") (pintype "power_in"))
      (node (ref "U5") (pin "39_9") (pinfunction "GND_39_9") (pintype "power_in"))
      (node (ref "U6") (pin "1") (pinfunction "GND_1") (pintype "passive"))
    )
    (net (code "69") (name "Net-(D1-A)") (class "Default")
      (node (ref "D1") (pin "1") (pinfunction "A_1") (pintype "passive"))
      (node (ref "J14") (pin "A4/B9") (pinfunction "VBUS_A4/B9") (pintype "power_in"))
      (node (ref "J14") (pin "B4/A9") (pinfunction "VBUS_B4/A9") (pintype "power_in"))
    )
    (net (code "70") (name "Net-(LED1-Pad1)") (class "Default")
      (node (ref "LED1") (pin "1") (pinfunction "1_1") (pintype "passive"))
      (node (ref "R13") (pin "1") (pinfunction "1_1") (pintype "passive"))
    )
    (net (code "71") (name "Net-(LED2-Pad1)") (class "Default")
      (node (ref "LED2") (pin "1") (pinfunction "1_1") (pintype "passive"))
      (node (ref "R14") (pin "1") (pinfunction "1_1") (pintype "passive"))
    )
    (net (code "72") (name "Net-(Q1-B)") (class "Default")
      (node (ref "Q1") (pin "1") (pinfunction "B_1") (pintype "passive"))
      (node (ref "R12") (pin "2") (pinfunction "2_2") (pintype "passive"))
    )
    (net (code "73") (name "Net-(Q2-B)") (class "Default")
      (node (ref "Q2") (pin "1") (pinfunction "B_1") (pintype "passive"))
      (node (ref "R15") (pin "1") (pinfunction "1_1") (pintype "passive"))
    )
    (net (code "74") (name "Net-(U3-1A)") (class "Default")
      (node (ref "R1") (pin "1") (pinfunction "1_1") (pintype "passive"))
      (node (ref "U3") (pin "2") (pinfunction "1A_2") (pintype "input"))
    )
    (net (code "75") (name "Net-(U3-2A)") (class "Default")
      (node (ref "R2") (pin "1") (pinfunction "1_1") (pintype "passive"))
      (node (ref "U3") (pin "5") (pinfunction "2A_5") (pintype "input"))
    )
    (net (code "76") (name "Net-(U3-3A)") (class "Default")
      (node (ref "R3") (pin "1") (pinfunction "1_1") (pintype "passive"))
      (node (ref "U3") (pin "9") (pinfunction "3A_9") (pintype "input"))
    )
    (net (code "77") (name "Net-(U3-4A)") (class "Default")
      (node (ref "R4") (pin "1") (pinfunction "1_1") (pintype "passive"))
      (node (ref "U3") (pin "12") (pinfunction "4A_12") (pintype "input"))
    )
    (net (code "78") (name "Net-(U4-~{RESET})") (class "Default")
      (node (ref "R5") (pin "1") (pinfunction "1_1") (pintype "passive"))
      (node (ref "U4") (pin "3") (pinfunction "~{RESET}_3") (pintype "input"))
    )
    (net (code "79") (name "VCC") (class "Default")
      (node (ref "C2") (pin "2") (pinfunction "2_2") (pintype "passive"))
      (node (ref "C3") (pin "2") (pinfunction "2_2") (pintype "passive"))
      (node (ref "C7") (pin "1") (pinfunction "1_1") (pintype "passive"))
      (node (ref "C7") (pin "2") (pinfunction "2_2") (pintype "passive"))
      (node (ref "C8") (pin "2") (pinfunction "2_2") (pintype "passive"))
      (node (ref "J1") (pin "P4") (pinfunction "VDD_P4") (pintype "power_in"))
      (node (ref "J12") (pin "5") (pinfunction "5_5") (pintype "passive"))
      (node (ref "J12") (pin "6") (pinfunction "6_6") (pintype "passive"))
      (node (ref "J12") (pin "7") (pinfunction "7_7") (pintype "passive"))
      (node (ref "J2") (pin "3") (pinfunction "3_3") (pintype "passive"))
      (node (ref "J3") (pin "3") (pinfunction "3_3") (pintype "passive"))
      (node (ref "R13") (pin "2") (pinfunction "2_2") (pintype "passive"))
      (node (ref "R14") (pin "2") (pinfunction "2_2") (pintype "passive"))
      (node (ref "R5") (pin "2") (pinfunction "2_2") (pintype "passive"))
      (node (ref "R6") (pin "2") (pinfunction "2_2") (pintype "passive"))
      (node (ref "R7") (pin "2") (pinfunction "2_2") (pintype "passive"))
      (node (ref "R8") (pin "2") (pinfunction "2_2") (pintype "passive"))
      (node (ref "U1") (pin "19") (pinfunction "STBY_19") (pintype "input"))
      (node (ref "U2") (pin "16") (pinfunction "VCC_16") (pintype "passive"))
      (node (ref "U3") (pin "14") (pinfunction "VCC_14") (pintype "power_in"))
      (node (ref "U4") (pin "24") (pinfunction "VCC_24") (pintype "power_in"))
      (node (ref "U5") (pin "2") (pinfunction "3V3_2") (pintype "power_in"))
      (node (ref "U6") (pin "4") (pinfunction "3V_4") (pintype "passive"))
    )
    (net (code "80") (name "unconnected-(J1-CD-PadP9)") (class "Default")
      (node (ref "J1") (pin "P9") (pinfunction "CD_P9") (pintype "passive"))
    )
    (net (code "81") (name "unconnected-(J1-DAT1-PadP8)") (class "Default")
      (node (ref "J1") (pin "P8") (pinfunction "DAT1_P8") (pintype "bidirectional"))
    )
    (net (code "82") (name "unconnected-(J1-DAT2-PadP1)") (class "Default")
      (node (ref "J1") (pin "P1") (pinfunction "DAT2_P1") (pintype "bidirectional"))
    )
    (net (code "83") (name "unconnected-(J2-MNT_1-Pad7)") (class "Default")
      (node (ref "J2") (pin "7") (pinfunction "MNT_1_7") (pintype "passive"))
    )
    (net (code "84") (name "unconnected-(J2-MNT_2-Pad8)") (class "Default")
      (node (ref "J2") (pin "8") (pinfunction "MNT_2_8") (pintype "passive"))
    )
    (net (code "85") (name "unconnected-(J3-MNT_1-Pad7)") (class "Default")
      (node (ref "J3") (pin "7") (pinfunction "MNT_1_7") (pintype "passive"))
    )
    (net (code "86") (name "unconnected-(J3-MNT_2-Pad8)") (class "Default")
      (node (ref "J3") (pin "8") (pinfunction "MNT_2_8") (pintype "passive"))
    )
    (net (code "87") (name "unconnected-(J4-S-PadP1)") (class "Default")
      (node (ref "J4") (pin "P1") (pinfunction "S_P1") (pintype "passive"))
    )
    (net (code "88") (name "unconnected-(J4-S-PadP2)") (class "Default")
      (node (ref "J4") (pin "P2") (pinfunction "S_P2") (pintype "passive"))
    )
    (net (code "89") (name "unconnected-(J5-S-PadP1)") (class "Default")
      (node (ref "J5") (pin "P1") (pinfunction "S_P1") (pintype "passive"))
    )
    (net (code "90") (name "unconnected-(J5-S-PadP2)") (class "Default")
      (node (ref "J5") (pin "P2") (pinfunction "S_P2") (pintype "passive"))
    )
    (net (code "91") (name "unconnected-(J6-S-PadP1)") (class "Default")
      (node (ref "J6") (pin "P1") (pinfunction "S_P1") (pintype "passive"))
    )
    (net (code "92") (name "unconnected-(J6-S-PadP2)") (class "Default")
      (node (ref "J6") (pin "P2") (pinfunction "S_P2") (pintype "passive"))
    )
    (net (code "93") (name "unconnected-(J7-S-PadP1)") (class "Default")
      (node (ref "J7") (pin "P1") (pinfunction "S_P1") (pintype "passive"))
    )
    (net (code "94") (name "unconnected-(J7-S-PadP2)") (class "Default")
      (node (ref "J7") (pin "P2") (pinfunction "S_P2") (pintype "passive"))
    )
    (net (code "95") (name "unconnected-(J8-S-PadP1)") (class "Default")
      (node (ref "J8") (pin "P1") (pinfunction "S_P1") (pintype "passive"))
    )
    (net (code "96") (name "unconnected-(J8-S-PadP2)") (class "Default")
      (node (ref "J8") (pin "P2") (pinfunction "S_P2") (pintype "passive"))
    )
    (net (code "97") (name "unconnected-(J9-S-PadP1)") (class "Default")
      (node (ref "J9") (pin "P1") (pinfunction "S_P1") (pintype "passive"))
    )
    (net (code "98") (name "unconnected-(J9-S-PadP2)") (class "Default")
      (node (ref "J9") (pin "P2") (pinfunction "S_P2") (pintype "passive"))
    )
    (net (code "99") (name "unconnected-(J10-S-PadP1)") (class "Default")
      (node (ref "J10") (pin "P1") (pinfunction "S_P1") (pintype "passive"))
    )
    (net (code "100") (name "unconnected-(J10-S-PadP2)") (class "Default")
      (node (ref "J10") (pin "P2") (pinfunction "S_P2") (pintype "passive"))
    )
    (net (code "101") (name "unconnected-(J11-S-PadP1)") (class "Default")
      (node (ref "J11") (pin "P1") (pinfunction "S_P1") (pintype "passive"))
    )
    (net (code "102") (name "unconnected-(J11-S-PadP2)") (class "Default")
      (node (ref "J11") (pin "P2") (pinfunction "S_P2") (pintype "passive"))
    )
    (net (code "103") (name "unconnected-(J12-Pad4)") (class "Default")
      (node (ref "J12") (pin "4") (pinfunction "4_4") (pintype "passive"))
    )
    (net (code "104") (name "unconnected-(J12-Pad8)") (class "Default")
      (node (ref "J12") (pin "8") (pinfunction "8_8") (pintype "passive"))
    )
    (net (code "105") (name "unconnected-(J12-SHIELD-PadS1)") (class "Default")
      (node (ref "J12") (pin "S1") (pinfunction "SHIELD_S1") (pintype "passive"))
    )
    (net (code "106") (name "unconnected-(J12-SHIELD-PadS2)") (class "Default")
      (node (ref "J12") (pin "S2") (pinfunction "SHIELD_S2") (pintype "passive"))
    )
    (net (code "107") (name "unconnected-(J13-SHIELD-PadS1)") (class "Default")
      (node (ref "J13") (pin "S1") (pinfunction "SHIELD_S1") (pintype "passive"))
    )
    (net (code "108") (name "unconnected-(J13-SHIELD-PadS2)") (class "Default")
      (node (ref "J13") (pin "S2") (pinfunction "SHIELD_S2") (pintype "passive"))
    )
    (net (code "109") (name "unconnected-(J14-SBU1-PadA8)") (class "Default")
      (node (ref "J14") (pin "A8") (pinfunction "SBU1_A8") (pintype "bidirectional"))
    )
    (net (code "110") (name "unconnected-(J14-SBU2-PadB8)") (class "Default")
      (node (ref "J14") (pin "B8") (pinfunction "SBU2_B8") (pintype "bidirectional"))
    )
    (net (code "111") (name "unconnected-(U2-INT-Pad13)") (class "Default")
      (node (ref "U2") (pin "13") (pinfunction "INT_13") (pintype "open_collector"))
    )
    (net (code "112") (name "unconnected-(U2-IO4-Pad9)") (class "Default")
      (node (ref "U2") (pin "9") (pinfunction "IO4_9") (pintype "bidirectional"))
    )
    (net (code "113") (name "unconnected-(U2-IO5-Pad10)") (class "Default")
      (node (ref "U2") (pin "10") (pinfunction "IO5_10") (pintype "bidirectional"))
    )
    (net (code "114") (name "unconnected-(U2-IO6-Pad11)") (class "Default")
      (node (ref "U2") (pin "11") (pinfunction "IO6_11") (pintype "bidirectional"))
    )
    (net (code "115") (name "unconnected-(U2-IO7-Pad12)") (class "Default")
      (node (ref "U2") (pin "12") (pinfunction "IO7_12") (pintype "bidirectional"))
    )
    (net (code "116") (name "unconnected-(U5-SCK{slash}CLK-Pad20)") (class "Default")
      (node (ref "U5") (pin "20") (pinfunction "SCK/CLK_20") (pintype "bidirectional"))
    )
    (net (code "117") (name "unconnected-(U5-SCS{slash}CMD-Pad19)") (class "Default")
      (node (ref "U5") (pin "19") (pinfunction "SCS/CMD_19") (pintype "bidirectional"))
    )
    (net (code "118") (name "unconnected-(U5-SDI{slash}SD1-Pad22)") (class "Default")
      (node (ref "U5") (pin "22") (pinfunction "SDI/SD1_22") (pintype "bidirectional"))
    )
    (net (code "119") (name "unconnected-(U5-SDO{slash}SD0-Pad21)") (class "Default")
      (node (ref "U5") (pin "21") (pinfunction "SDO/SD0_21") (pintype "bidirectional"))
    )
    (net (code "120") (name "unconnected-(U5-SHD{slash}SD2-Pad17)") (class "Default")
      (node (ref "U5") (pin "17") (pinfunction "SHD/SD2_17") (pintype "bidirectional"))
    )
    (net (code "121") (name "unconnected-(U5-SWP{slash}SD3-Pad18)") (class "Default")
      (node (ref "U5") (pin "18") (pinfunction "SWP/SD3_18") (pintype "bidirectional"))
    )
    (net (code "122") (name "unconnected-(U6-CTR#-Pad9)") (class "Default")
      (node (ref "U6") (pin "9") (pinfunction "CTR#_9") (pintype "passive"))
    )
    (net (code "123") (name "unconnected-(U6-DCD#-Pad12)") (class "Default")
      (node (ref "U6") (pin "12") (pinfunction "DCD#_12") (pintype "passive"))
    )
    (net (code "124") (name "unconnected-(U6-DSR#-Pad10)") (class "Default")
      (node (ref "U6") (pin "10") (pinfunction "DSR#_10") (pintype "passive"))
    )
    (net (code "125") (name "unconnected-(U6-RI#-Pad11)") (class "Default")
      (node (ref "U6") (pin "11") (pinfunction "RI#_11") (pintype "passive"))
    )
    (net (code "126") (name "unconnected-(U6-RS232-Pad15)") (class "Default")
      (node (ref "U6") (pin "15") (pinfunction "RS232_15") (pintype "passive"))
    )
  )
)
